# LED_Inducator.net
KiCad netlist of a schematic drawn in Altium Designer
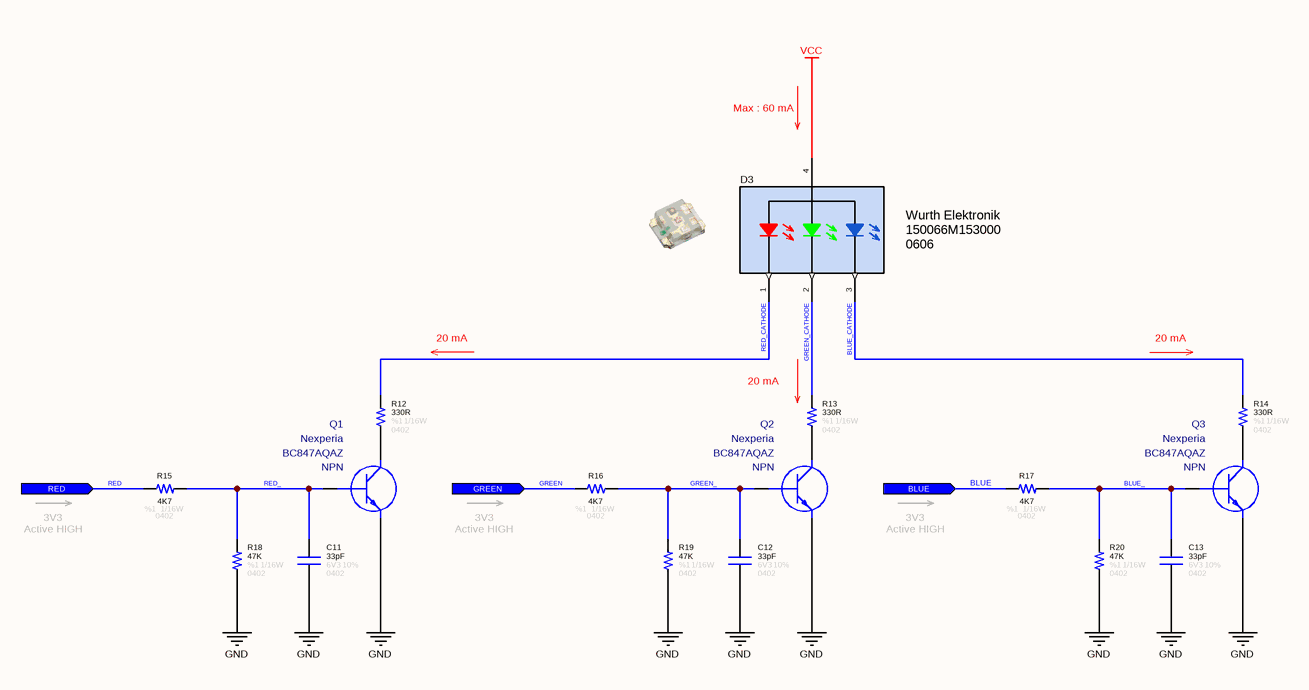
[diagram p0: LED Inducator.SchDoc]

(export (version "E")
  (design (tool "Eeschema 10.0.6"))
  (components
    (comp (ref "C11")
      (value "33pF")
      (footprint "CAPACITOR_0402")
      (description "Capacitor - 33pF [0402] (Ceramic)")
      (fields
        (field (name "MANUFACTURER PART NUMBER") "C0402C330J9RACAUTO")
        (field (name "TOLERANCE") "10%")
        (field (name "CASE") "0402")
        (field (name "VOLTAGE") "6V3")
      )
      (libsource (lib "P101DA_Library") (part "Capacitor - 33pF [0402-6V3]"))
    )
    (comp (ref "C12")
      (value "33pF")
      (footprint "CAPACITOR_0402")
      (description "Capacitor - 33pF [0402] (Ceramic)")
      (fields
        (field (name "MANUFACTURER PART NUMBER") "C0402C330J9RACAUTO")
        (field (name "TOLERANCE") "10%")
        (field (name "CASE") "0402")
        (field (name "VOLTAGE") "6V3")
      )
      (libsource (lib "P101DA_Library") (part "Capacitor - 33pF [0402-6V3]"))
    )
    (comp (ref "C13")
      (value "33pF")
      (footprint "CAPACITOR_0402")
      (description "Capacitor - 33pF [0402] (Ceramic)")
      (fields
        (field (name "MANUFACTURER PART NUMBER") "C0402C330J9RACAUTO")
        (field (name "TOLERANCE") "10%")
        (field (name "CASE") "0402")
        (field (name "VOLTAGE") "6V3")
      )
      (libsource (lib "P101DA_Library") (part "Capacitor - 33pF [0402-6V3]"))
    )
    (comp (ref "D3")
      (value "150066M153000")
      (footprint "Wurth_0606")
      (description "LED RGB DIFFUSED SMD")
      (fields
        (field (name "MANUFACTURER NAME") "Wurth Elektronik")
        (field (name "MANUFACTURER PART NUMBER") "150066M153000")
        (field (name "CASE") "0606")
      )
      (libsource (lib "P101DA_Library") (part "Diode - LED-RGB"))
    )
    (comp (ref "Q1")
      (value "BC847AQAZ")
      (footprint "SOT1215")
      (description "Bipolar NPN Transistors")
      (fields
        (field (name "MANUFACTURER NAME") "Nexperia")
        (field (name "MANUFACTURER PART NUMBER") "BC847AQAZ")
        (field (name "POLARITY") "NPN")
      )
      (libsource (lib "P101DA_Library") (part "Transistor - BC847"))
    )
    (comp (ref "Q2")
      (value "BC847AQAZ")
      (footprint "SOT1215")
      (description "Bipolar NPN Transistors")
      (fields
        (field (name "MANUFACTURER NAME") "Nexperia")
        (field (name "MANUFACTURER PART NUMBER") "BC847AQAZ")
        (field (name "POLARITY") "NPN")
      )
      (libsource (lib "P101DA_Library") (part "Transistor - BC847"))
    )
    (comp (ref "Q3")
      (value "BC847AQAZ")
      (footprint "SOT1215")
      (description "Bipolar NPN Transistors")
      (fields
        (field (name "MANUFACTURER NAME") "Nexperia")
        (field (name "MANUFACTURER PART NUMBER") "BC847AQAZ")
        (field (name "POLARITY") "NPN")
      )
      (libsource (lib "P101DA_Library") (part "Transistor - BC847"))
    )
    (comp (ref "R12")
      (value "330R")
      (footprint "RESISTOR_0402")
      (description "Thick Film Resistors - SMD 1/16 W 330 Ohm 1%")
      (fields
        (field (name "MANUFACTURER PART NUMBER") "CRCW0402330RFKED")
        (field (name "CASE") "0402")
        (field (name "TOLERANCE") "%1")
        (field (name "POWER") "1/16W")
        (field (name "Comment") "330R - 0402 - %1 - 1/16W")
      )
      (libsource (lib "P101DA_Library") (part "Resistor - 330R [0402]"))
    )
    (comp (ref "R13")
      (value "330R")
      (footprint "RESISTOR_0402")
      (description "Thick Film Resistors - SMD 1/16 W 330 Ohm 1%")
      (fields
        (field (name "MANUFACTURER PART NUMBER") "CRCW0402330RFKED")
        (field (name "CASE") "0402")
        (field (name "TOLERANCE") "%1")
        (field (name "POWER") "1/16W")
        (field (name "Comment") "330R - 0402 - %1 - 1/16W")
      )
      (libsource (lib "P101DA_Library") (part "Resistor - 330R [0402]"))
    )
    (comp (ref "R14")
      (value "330R")
      (footprint "RESISTOR_0402")
      (description "Thick Film Resistors - SMD 1/16 W 330 Ohm 1%")
      (fields
        (field (name "MANUFACTURER PART NUMBER") "CRCW0402330RFKED")
        (field (name "CASE") "0402")
        (field (name "TOLERANCE") "%1")
        (field (name "POWER") "1/16W")
        (field (name "Comment") "330R - 0402 - %1 - 1/16W")
      )
      (libsource (lib "P101DA_Library") (part "Resistor - 330R [0402]"))
    )
    (comp (ref "R15")
      (value "4K7")
      (footprint "RESISTOR_0402")
      (description "Thick Film Resistors - SMD 1/16 W 4.7 KOhm 1%")
      (fields
        (field (name "MANUFACTURER PART NUMBER") "CRCW04024K70FKED")
        (field (name "TOLERANCE") "%1")
        (field (name "CASE") "0402")
        (field (name "POWER") "1/16W")
        (field (name "Comment") "4K7 - 0402 - %1 - 1/16W")
      )
      (libsource (lib "P101DA_Library") (part "Resistor - 4K7 [0402]"))
    )
    (comp (ref "R16")
      (value "4K7")
      (footprint "RESISTOR_0402")
      (description "Thick Film Resistors - SMD 1/16 W 4.7 KOhm 1%")
      (fields
        (field (name "MANUFACTURER PART NUMBER") "CRCW04024K70FKED")
        (field (name "TOLERANCE") "%1")
        (field (name "CASE") "0402")
        (field (name "POWER") "1/16W")
        (field (name "Comment") "4K7 - 0402 - %1 - 1/16W")
      )
      (libsource (lib "P101DA_Library") (part "Resistor - 4K7 [0402]"))
    )
    (comp (ref "R17")
      (value "4K7")
      (footprint "RESISTOR_0402")
      (description "Thick Film Resistors - SMD 1/16 W 4.7 KOhm 1%")
      (fields
        (field (name "MANUFACTURER PART NUMBER") "CRCW04024K70FKED")
        (field (name "TOLERANCE") "%1")
        (field (name "CASE") "0402")
        (field (name "POWER") "1/16W")
        (field (name "Comment") "4K7 - 0402 - %1 - 1/16W")
      )
      (libsource (lib "P101DA_Library") (part "Resistor - 4K7 [0402]"))
    )
    (comp (ref "R18")
      (value "47K")
      (footprint "RESISTOR_0402")
      (description "Thick Film Resistors - SMD 1/16 W 47 KOhm 1%")
      (fields
        (field (name "MANUFACTURER PART NUMBER") "CRCW040247K0FKED")
        (field (name "TOLERANCE") "%1")
        (field (name "CASE") "0402")
        (field (name "POWER") "1/16W")
        (field (name "Comment") "47K - 0402 - %1 - 1/16W")
      )
      (libsource (lib "P101DA_Library") (part "Resistor - 47K [0402]"))
    )
    (comp (ref "R19")
      (value "47K")
      (footprint "RESISTOR_0402")
      (description "Thick Film Resistors - SMD 1/16 W 47 KOhm 1%")
      (fields
        (field (name "MANUFACTURER PART NUMBER") "CRCW040247K0FKED")
        (field (name "TOLERANCE") "%1")
        (field (name "CASE") "0402")
        (field (name "POWER") "1/16W")
        (field (name "Comment") "47K - 0402 - %1 - 1/16W")
      )
      (libsource (lib "P101DA_Library") (part "Resistor - 47K [0402]"))
    )
    (comp (ref "R20")
      (value "47K")
      (footprint "RESISTOR_0402")
      (description "Thick Film Resistors - SMD 1/16 W 47 KOhm 1%")
      (fields
        (field (name "MANUFACTURER PART NUMBER") "CRCW040247K0FKED")
        (field (name "TOLERANCE") "%1")
        (field (name "CASE") "0402")
        (field (name "POWER") "1/16W")
        (field (name "Comment") "47K - 0402 - %1 - 1/16W")
      )
      (libsource (lib "P101DA_Library") (part "Resistor - 47K [0402]"))
    )
  )
  (nets
    (net (code "1") (name "/BLUE") (class "Default")
      (node (ref "R17") (pin "2") (pinfunction "2_2") (pintype "passive"))
    )
    (net (code "2") (name "/BLUE_") (class "Default")
      (node (ref "C13") (pin "2") (pinfunction "2_2") (pintype "passive"))
      (node (ref "Q3") (pin "1") (pinfunction "B_1") (pintype "passive"))
      (node (ref "R17") (pin "1") (pinfunction "1_1") (pintype "passive"))
      (node (ref "R20") (pin "2") (pinfunction "2_2") (pintype "passive"))
    )
    (net (code "3") (name "/BLUE_CATHODE") (class "Default")
      (node (ref "D3") (pin "3") (pinfunction "3_3") (pintype "output"))
      (node (ref "R14") (pin "2") (pinfunction "2_2") (pintype "passive"))
    )
    (net (code "4") (name "/GREEN") (class "Default")
      (node (ref "R16") (pin "2") (pinfunction "2_2") (pintype "passive"))
    )
    (net (code "5") (name "/GREEN_") (class "Default")
      (node (ref "C12") (pin "2") (pinfunction "2_2") (pintype "passive"))
      (node (ref "Q2") (pin "1") (pinfunction "B_1") (pintype "passive"))
      (node (ref "R16") (pin "1") (pinfunction "1_1") (pintype "passive"))
      (node (ref "R19") (pin "2") (pinfunction "2_2") (pintype "passive"))
    )
    (net (code "6") (name "/GREEN_CATHODE") (class "Default")
      (node (ref "D3") (pin "2") (pinfunction "2_2") (pintype "output"))
      (node (ref "R13") (pin "2") (pinfunction "2_2") (pintype "passive"))
    )
    (net (code "7") (name "/RED") (class "Default")
      (node (ref "R15") (pin "2") (pinfunction "2_2") (pintype "passive"))
    )
    (net (code "8") (name "/RED_") (class "Default")
      (node (ref "C11") (pin "2") (pinfunction "2_2") (pintype "passive"))
      (node (ref "Q1") (pin "1") (pinfunction "B_1") (pintype "passive"))
      (node (ref "R15") (pin "1") (pinfunction "1_1") (pintype "passive"))
      (node (ref "R18") (pin "2") (pinfunction "2_2") (pintype "passive"))
    )
    (net (code "9") (name "/RED_CATHODE") (class "Default")
      (node (ref "D3") (pin "1") (pinfunction "1_1") (pintype "output"))
      (node (ref "R12") (pin "2") (pinfunction "2_2") (pintype "passive"))
    )
    (net (code "10") (name "GND") (class "Default")
      (node (ref "C11") (pin "1") (pinfunction "1_1") (pintype "passive"))
      (node (ref "C12") (pin "1") (pinfunction "1_1") (pintype "passive"))
      (node (ref "C13") (pin "1") (pinfunction "1_1") (pintype "passive"))
      (node (ref "Q1") (pin "2") (pinfunction "E_2") (pintype "passive"))
      (node (ref "Q2") (pin "2") (pinfunction "E_2") (pintype "passive"))
      (node (ref "Q3") (pin "2") (pinfunction "E_2") (pintype "passive"))
      (node (ref "R18") (pin "1") (pinfunction "1_1") (pintype "passive"))
      (node (ref "R19") (pin "1") (pinfunction "1_1") (pintype "passive"))
      (node (ref "R20") (pin "1") (pinfunction "1_1") (pintype "passive"))
    )
    (net (code "11") (name "Net-(Q1-C)") (class "Default")
      (node (ref "Q1") (pin "3") (pinfunction "C_3") (pintype "passive"))
      (node (ref "R12") (pin "1") (pinfunction "1_1") (pintype "passive"))
    )
    (net (code "12") (name "Net-(Q2-C)") (class "Default")
      (node (ref "Q2") (pin "3") (pinfunction "C_3") (pintype "passive"))
      (node (ref "R13") (pin "1") (pinfunction "1_1") (pintype "passive"))
    )
    (net (code "13") (name "Net-(Q3-C)") (class "Default")
      (node (ref "Q3") (pin "3") (pinfunction "C_3") (pintype "passive"))
      (node (ref "R14") (pin "1") (pinfunction "1_1") (pintype "passive"))
    )
    (net (code "14") (name "VCC") (class "Default")
      (node (ref "D3") (pin "4") (pinfunction "4_4") (pintype "power_in"))
    )
  )
)
